# 0_Overview.net
KiCad netlist of a schematic drawn in Altium Designer
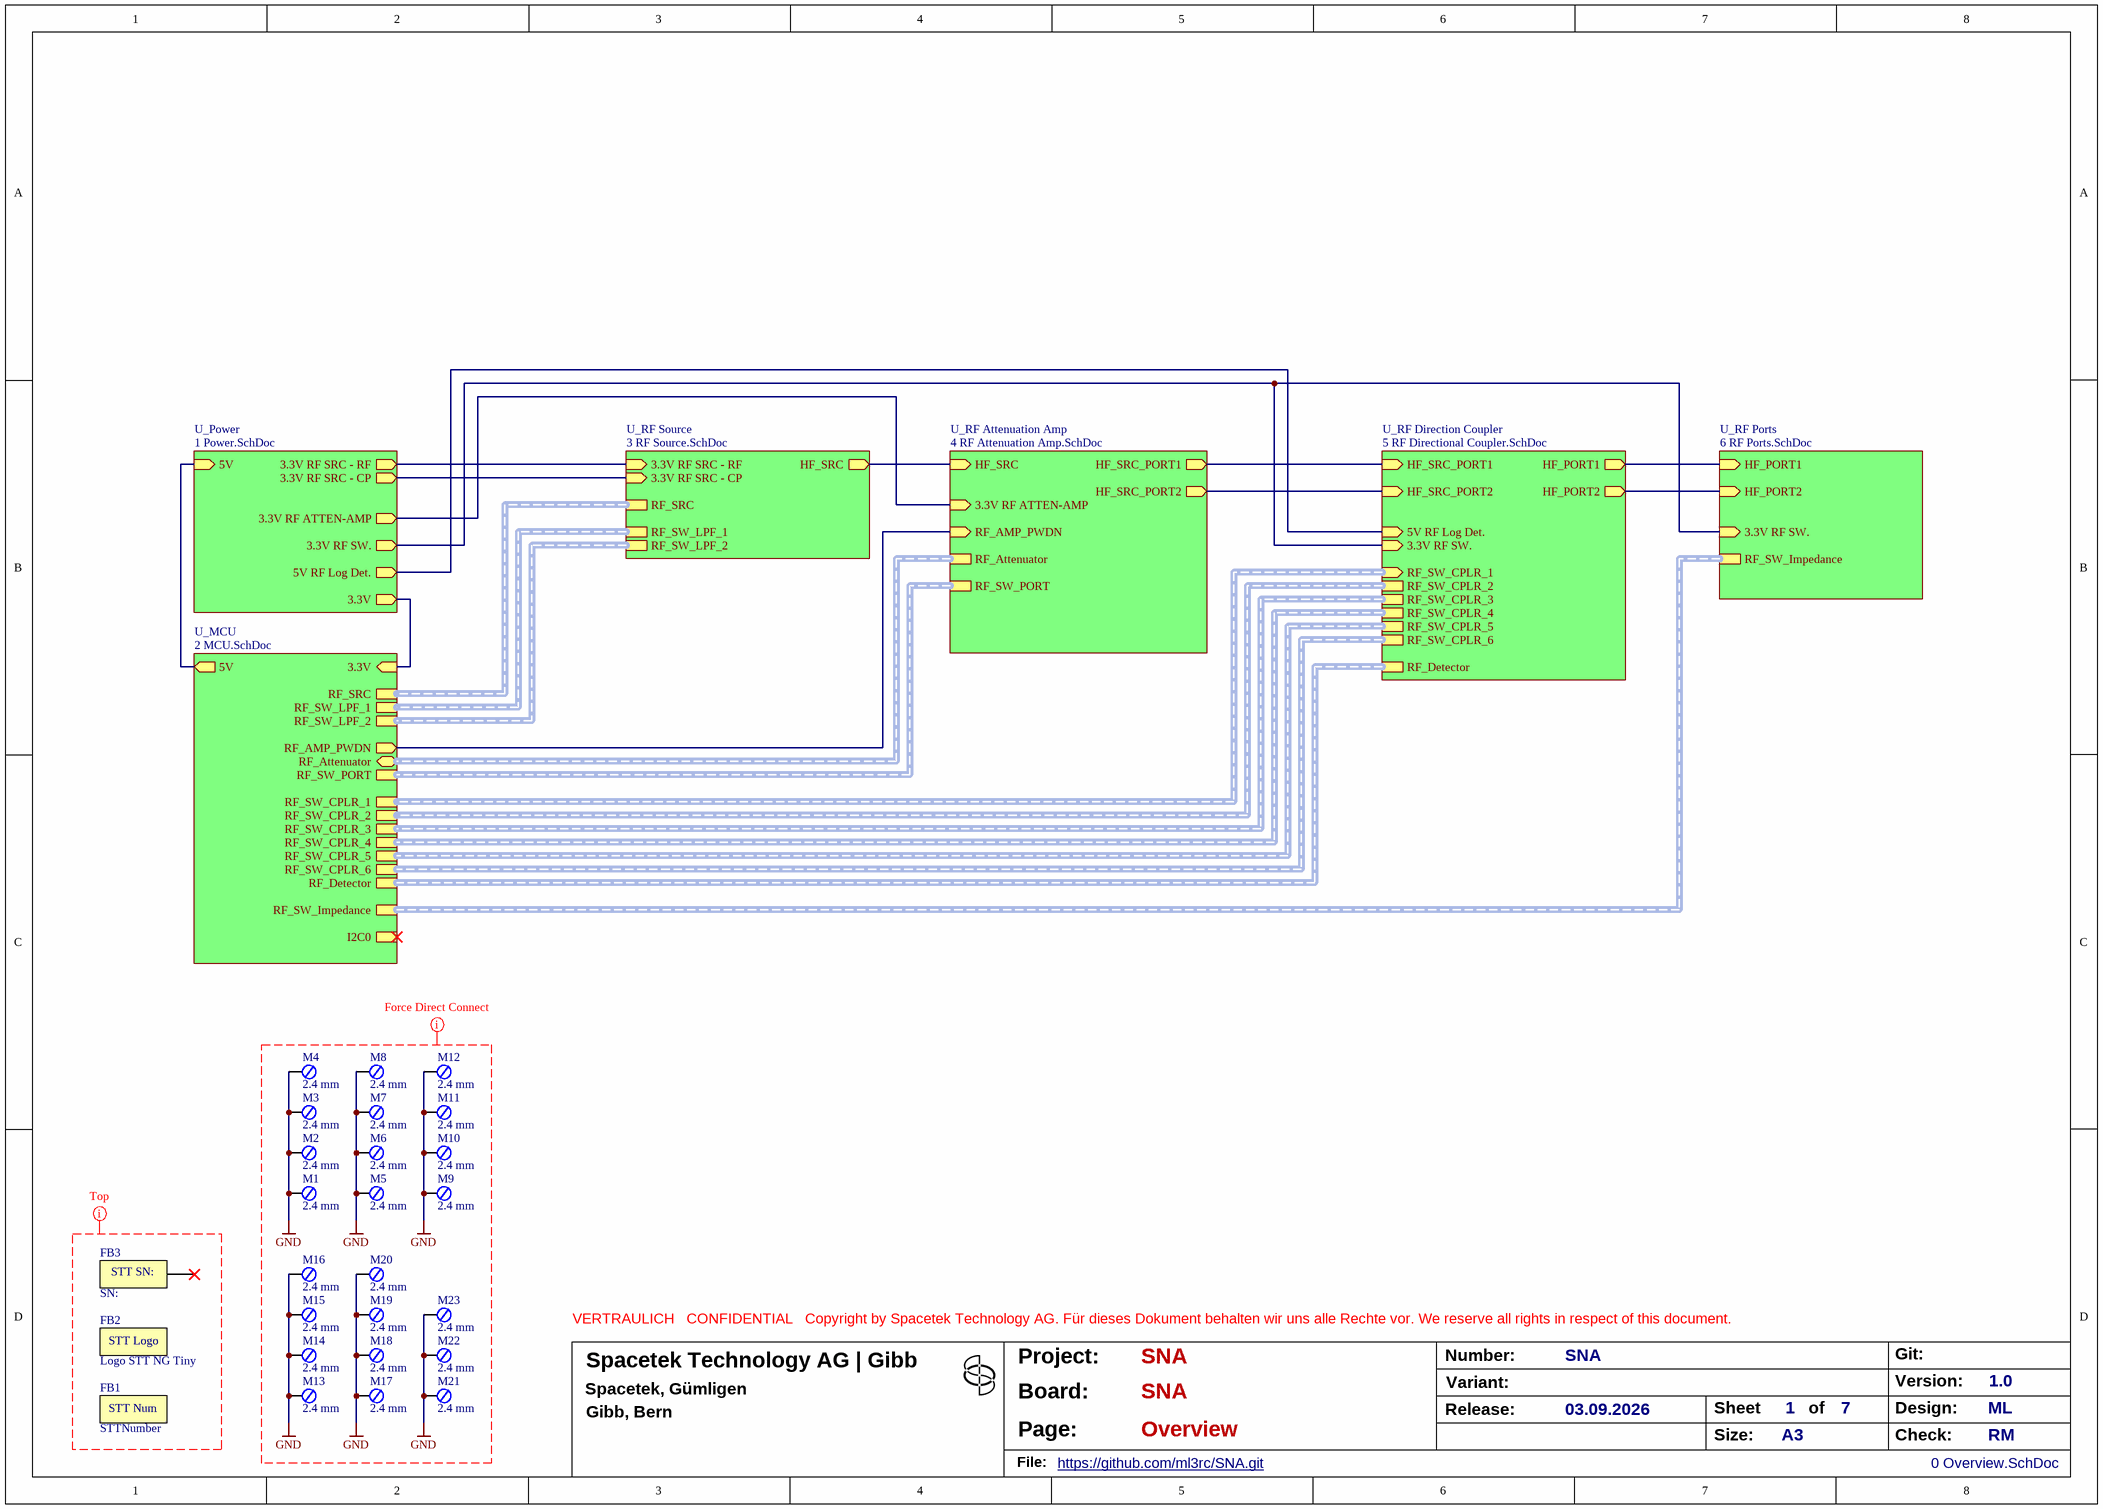
[diagram p0: 0 Overview.SchDoc]

(export (version "E")
  (design (tool "Eeschema 10.0.6"))
  (components
    (comp (ref "FB1")
      (value "STTNumber")
      (footprint "STT--DO--STT-Number")
      (description "Fabrication Object STTNumber SMD--STTNumber")
      (libsource (lib "Spacetek Technology AG") (part "FB--Number"))
    )
    (comp (ref "FB2")
      (value "Logo STT NG Tiny")
      (footprint "STT--DO--Logo-New")
      (description "Fabrication Object Logo STT NG SMD--LOGO")
      (libsource (lib "Spacetek Technology AG") (part "FB--Logo"))
    )
    (comp (ref "FB3")
      (value "SN:")
      (footprint "STT--DO--SN")
      (description "Fabrication Object SN: SMD--SN")
      (libsource (lib "Spacetek Technology AG") (part "FB--SN{colon}"))
    )
    (comp (ref "M1")
      (value "2.4 mm")
      (footprint "STT--DO--Hole-2.4-3.0")
      (description "Hole  THT--Hole 2.4 / 3.0")
      (libsource (lib "Spacetek Technology AG") (part "M--Mounting-Hole"))
    )
    (comp (ref "M2")
      (value "2.4 mm")
      (footprint "STT--DO--Hole-2.4-3.0")
      (description "Hole  THT--Hole 2.4 / 3.0")
      (libsource (lib "Spacetek Technology AG") (part "M--Mounting-Hole"))
    )
    (comp (ref "M3")
      (value "2.4 mm")
      (footprint "STT--DO--Hole-2.4-3.0")
      (description "Hole  THT--Hole 2.4 / 3.0")
      (libsource (lib "Spacetek Technology AG") (part "M--Mounting-Hole"))
    )
    (comp (ref "M4")
      (value "2.4 mm")
      (footprint "STT--DO--Hole-2.4-3.0")
      (description "Hole  THT--Hole 2.4 / 3.0")
      (libsource (lib "Spacetek Technology AG") (part "M--Mounting-Hole"))
    )
    (comp (ref "M5")
      (value "2.4 mm")
      (footprint "STT--DO--Hole-2.4-3.0")
      (description "Hole  THT--Hole 2.4 / 3.0")
      (libsource (lib "Spacetek Technology AG") (part "M--Mounting-Hole"))
    )
    (comp (ref "M6")
      (value "2.4 mm")
      (footprint "STT--DO--Hole-2.4-3.0")
      (description "Hole  THT--Hole 2.4 / 3.0")
      (libsource (lib "Spacetek Technology AG") (part "M--Mounting-Hole"))
    )
    (comp (ref "M7")
      (value "2.4 mm")
      (footprint "STT--DO--Hole-2.4-3.0")
      (description "Hole  THT--Hole 2.4 / 3.0")
      (libsource (lib "Spacetek Technology AG") (part "M--Mounting-Hole"))
    )
    (comp (ref "M8")
      (value "2.4 mm")
      (footprint "STT--DO--Hole-2.4-3.0")
      (description "Hole  THT--Hole 2.4 / 3.0")
      (libsource (lib "Spacetek Technology AG") (part "M--Mounting-Hole"))
    )
    (comp (ref "M9")
      (value "2.4 mm")
      (footprint "STT--DO--Hole-2.4-3.0")
      (description "Hole  THT--Hole 2.4 / 3.0")
      (libsource (lib "Spacetek Technology AG") (part "M--Mounting-Hole"))
    )
    (comp (ref "M10")
      (value "2.4 mm")
      (footprint "STT--DO--Hole-2.4-3.0")
      (description "Hole  THT--Hole 2.4 / 3.0")
      (libsource (lib "Spacetek Technology AG") (part "M--Mounting-Hole"))
    )
    (comp (ref "M11")
      (value "2.4 mm")
      (footprint "STT--DO--Hole-2.4-3.0")
      (description "Hole  THT--Hole 2.4 / 3.0")
      (libsource (lib "Spacetek Technology AG") (part "M--Mounting-Hole"))
    )
    (comp (ref "M12")
      (value "2.4 mm")
      (footprint "STT--DO--Hole-2.4-3.0")
      (description "Hole  THT--Hole 2.4 / 3.0")
      (libsource (lib "Spacetek Technology AG") (part "M--Mounting-Hole"))
    )
    (comp (ref "M13")
      (value "2.4 mm")
      (footprint "STT--DO--Hole-2.4-3.0")
      (description "Hole  THT--Hole 2.4 / 3.0")
      (libsource (lib "Spacetek Technology AG") (part "M--Mounting-Hole"))
    )
    (comp (ref "M14")
      (value "2.4 mm")
      (footprint "STT--DO--Hole-2.4-3.0")
      (description "Hole  THT--Hole 2.4 / 3.0")
      (libsource (lib "Spacetek Technology AG") (part "M--Mounting-Hole"))
    )
    (comp (ref "M15")
      (value "2.4 mm")
      (footprint "STT--DO--Hole-2.4-3.0")
      (description "Hole  THT--Hole 2.4 / 3.0")
      (libsource (lib "Spacetek Technology AG") (part "M--Mounting-Hole"))
    )
    (comp (ref "M16")
      (value "2.4 mm")
      (footprint "STT--DO--Hole-2.4-3.0")
      (description "Hole  THT--Hole 2.4 / 3.0")
      (libsource (lib "Spacetek Technology AG") (part "M--Mounting-Hole"))
    )
    (comp (ref "M17")
      (value "2.4 mm")
      (footprint "STT--DO--Hole-2.4-3.0")
      (description "Hole  THT--Hole 2.4 / 3.0")
      (libsource (lib "Spacetek Technology AG") (part "M--Mounting-Hole"))
    )
    (comp (ref "M18")
      (value "2.4 mm")
      (footprint "STT--DO--Hole-2.4-3.0")
      (description "Hole  THT--Hole 2.4 / 3.0")
      (libsource (lib "Spacetek Technology AG") (part "M--Mounting-Hole"))
    )
    (comp (ref "M19")
      (value "2.4 mm")
      (footprint "STT--DO--Hole-2.4-3.0")
      (description "Hole  THT--Hole 2.4 / 3.0")
      (libsource (lib "Spacetek Technology AG") (part "M--Mounting-Hole"))
    )
    (comp (ref "M20")
      (value "2.4 mm")
      (footprint "STT--DO--Hole-2.4-3.0")
      (description "Hole  THT--Hole 2.4 / 3.0")
      (libsource (lib "Spacetek Technology AG") (part "M--Mounting-Hole"))
    )
    (comp (ref "M21")
      (value "2.4 mm")
      (footprint "STT--DO--Hole-2.4-3.0")
      (description "Hole  THT--Hole 2.4 / 3.0")
      (libsource (lib "Spacetek Technology AG") (part "M--Mounting-Hole"))
    )
    (comp (ref "M22")
      (value "2.4 mm")
      (footprint "STT--DO--Hole-2.4-3.0")
      (description "Hole  THT--Hole 2.4 / 3.0")
      (libsource (lib "Spacetek Technology AG") (part "M--Mounting-Hole"))
    )
    (comp (ref "M23")
      (value "2.4 mm")
      (footprint "STT--DO--Hole-2.4-3.0")
      (description "Hole  THT--Hole 2.4 / 3.0")
      (libsource (lib "Spacetek Technology AG") (part "M--Mounting-Hole"))
    )
  )
  (nets
    (net (code "28") (name "GND") (class "Default")
      (node (ref "M1") (pin "1") (pinfunction "1_1") (pintype "passive"))
      (node (ref "M10") (pin "1") (pinfunction "1_1") (pintype "passive"))
      (node (ref "M11") (pin "1") (pinfunction "1_1") (pintype "passive"))
      (node (ref "M12") (pin "1") (pinfunction "1_1") (pintype "passive"))
      (node (ref "M13") (pin "1") (pinfunction "1_1") (pintype "passive"))
      (node (ref "M14") (pin "1") (pinfunction "1_1") (pintype "passive"))
      (node (ref "M15") (pin "1") (pinfunction "1_1") (pintype "passive"))
      (node (ref "M16") (pin "1") (pinfunction "1_1") (pintype "passive"))
      (node (ref "M17") (pin "1") (pinfunction "1_1") (pintype "passive"))
      (node (ref "M18") (pin "1") (pinfunction "1_1") (pintype "passive"))
      (node (ref "M19") (pin "1") (pinfunction "1_1") (pintype "passive"))
      (node (ref "M2") (pin "1") (pinfunction "1_1") (pintype "passive"))
      (node (ref "M20") (pin "1") (pinfunction "1_1") (pintype "passive"))
      (node (ref "M21") (pin "1") (pinfunction "1_1") (pintype "passive"))
      (node (ref "M22") (pin "1") (pinfunction "1_1") (pintype "passive"))
      (node (ref "M23") (pin "1") (pinfunction "1_1") (pintype "passive"))
      (node (ref "M3") (pin "1") (pinfunction "1_1") (pintype "passive"))
      (node (ref "M4") (pin "1") (pinfunction "1_1") (pintype "passive"))
      (node (ref "M5") (pin "1") (pinfunction "1_1") (pintype "passive"))
      (node (ref "M6") (pin "1") (pinfunction "1_1") (pintype "passive"))
      (node (ref "M7") (pin "1") (pinfunction "1_1") (pintype "passive"))
      (node (ref "M8") (pin "1") (pinfunction "1_1") (pintype "passive"))
      (node (ref "M9") (pin "1") (pinfunction "1_1") (pintype "passive"))
    )
    (net (code "29") (name "unconnected-(FB3-Pad1)") (class "Default")
      (node (ref "FB3") (pin "1") (pinfunction "1_1") (pintype "passive+no_connect"))
    )
  )
)
